# M050B.net
KiCad netlist of a schematic drawn in EAGLE
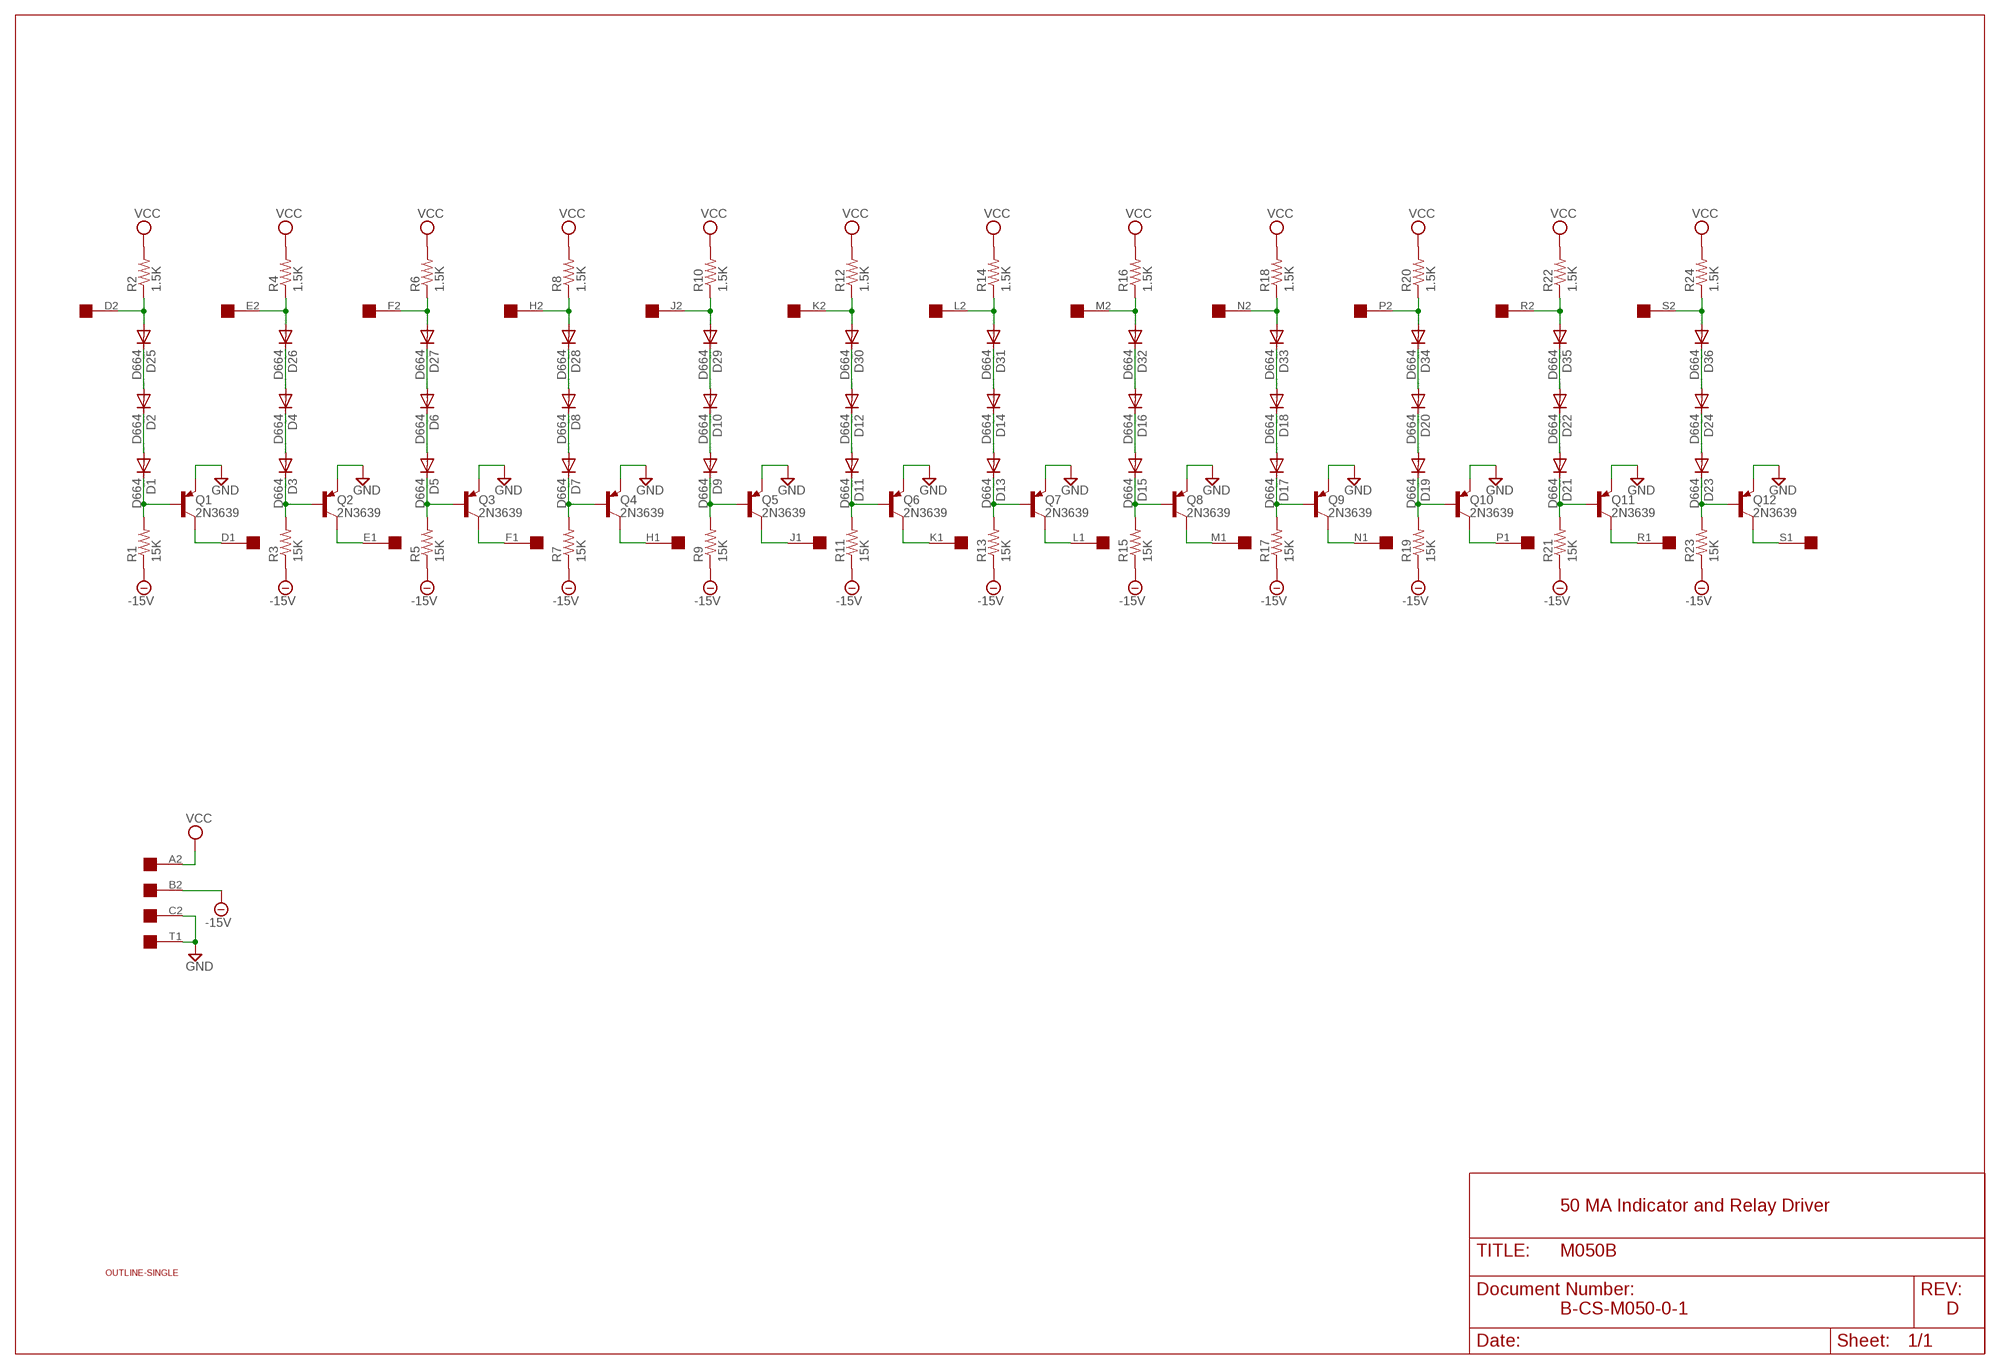
[diagram p0: schematic, sheet 1]

(export (version "E")
  (design (tool "Eeschema 10.0.6"))
  (components
    (comp (ref "D1")
      (value "D664")
      (footprint "eagle-import:DO35-10")
      (libsource (lib "eagle-import") (part "DIODE-DO35-10"))
    )
    (comp (ref "D2")
      (value "D664")
      (footprint "eagle-import:DO35-10")
      (libsource (lib "eagle-import") (part "DIODE-DO35-10"))
    )
    (comp (ref "D3")
      (value "D664")
      (footprint "eagle-import:DO35-10")
      (libsource (lib "eagle-import") (part "DIODE-DO35-10"))
    )
    (comp (ref "D4")
      (value "D664")
      (footprint "eagle-import:DO35-10")
      (libsource (lib "eagle-import") (part "DIODE-DO35-10"))
    )
    (comp (ref "D5")
      (value "D664")
      (footprint "eagle-import:DO35-10")
      (libsource (lib "eagle-import") (part "DIODE-DO35-10"))
    )
    (comp (ref "D6")
      (value "D664")
      (footprint "eagle-import:DO35-10")
      (libsource (lib "eagle-import") (part "DIODE-DO35-10"))
    )
    (comp (ref "D7")
      (value "D664")
      (footprint "eagle-import:DO35-10")
      (libsource (lib "eagle-import") (part "DIODE-DO35-10"))
    )
    (comp (ref "D8")
      (value "D664")
      (footprint "eagle-import:DO35-10")
      (libsource (lib "eagle-import") (part "DIODE-DO35-10"))
    )
    (comp (ref "D9")
      (value "D664")
      (footprint "eagle-import:DO35-10")
      (libsource (lib "eagle-import") (part "DIODE-DO35-10"))
    )
    (comp (ref "D10")
      (value "D664")
      (footprint "eagle-import:DO35-10")
      (libsource (lib "eagle-import") (part "DIODE-DO35-10"))
    )
    (comp (ref "D11")
      (value "D664")
      (footprint "eagle-import:DO35-10")
      (libsource (lib "eagle-import") (part "DIODE-DO35-10"))
    )
    (comp (ref "D12")
      (value "D664")
      (footprint "eagle-import:DO35-10")
      (libsource (lib "eagle-import") (part "DIODE-DO35-10"))
    )
    (comp (ref "D13")
      (value "D664")
      (footprint "eagle-import:DO35-10")
      (libsource (lib "eagle-import") (part "DIODE-DO35-10"))
    )
    (comp (ref "D14")
      (value "D664")
      (footprint "eagle-import:DO35-10")
      (libsource (lib "eagle-import") (part "DIODE-DO35-10"))
    )
    (comp (ref "D15")
      (value "D664")
      (footprint "eagle-import:DO35-10")
      (libsource (lib "eagle-import") (part "DIODE-DO35-10"))
    )
    (comp (ref "D16")
      (value "D664")
      (footprint "eagle-import:DO35-10")
      (libsource (lib "eagle-import") (part "DIODE-DO35-10"))
    )
    (comp (ref "D17")
      (value "D664")
      (footprint "eagle-import:DO35-10")
      (libsource (lib "eagle-import") (part "DIODE-DO35-10"))
    )
    (comp (ref "D18")
      (value "D664")
      (footprint "eagle-import:DO35-10")
      (libsource (lib "eagle-import") (part "DIODE-DO35-10"))
    )
    (comp (ref "D19")
      (value "D664")
      (footprint "eagle-import:DO35-10")
      (libsource (lib "eagle-import") (part "DIODE-DO35-10"))
    )
    (comp (ref "D20")
      (value "D664")
      (footprint "eagle-import:DO35-10")
      (libsource (lib "eagle-import") (part "DIODE-DO35-10"))
    )
    (comp (ref "D21")
      (value "D664")
      (footprint "eagle-import:DO35-10")
      (libsource (lib "eagle-import") (part "DIODE-DO35-10"))
    )
    (comp (ref "D22")
      (value "D664")
      (footprint "eagle-import:DO35-10")
      (libsource (lib "eagle-import") (part "DIODE-DO35-10"))
    )
    (comp (ref "D23")
      (value "D664")
      (footprint "eagle-import:DO35-10")
      (libsource (lib "eagle-import") (part "DIODE-DO35-10"))
    )
    (comp (ref "D24")
      (value "D664")
      (footprint "eagle-import:DO35-10")
      (libsource (lib "eagle-import") (part "DIODE-DO35-10"))
    )
    (comp (ref "D25")
      (value "D664")
      (footprint "eagle-import:DO35-10")
      (libsource (lib "eagle-import") (part "DIODE-DO35-10"))
    )
    (comp (ref "D26")
      (value "D664")
      (footprint "eagle-import:DO35-10")
      (libsource (lib "eagle-import") (part "DIODE-DO35-10"))
    )
    (comp (ref "D27")
      (value "D664")
      (footprint "eagle-import:DO35-10")
      (libsource (lib "eagle-import") (part "DIODE-DO35-10"))
    )
    (comp (ref "D28")
      (value "D664")
      (footprint "eagle-import:DO35-10")
      (libsource (lib "eagle-import") (part "DIODE-DO35-10"))
    )
    (comp (ref "D29")
      (value "D664")
      (footprint "eagle-import:DO35-10")
      (libsource (lib "eagle-import") (part "DIODE-DO35-10"))
    )
    (comp (ref "D30")
      (value "D664")
      (footprint "eagle-import:DO35-10")
      (libsource (lib "eagle-import") (part "DIODE-DO35-10"))
    )
    (comp (ref "D31")
      (value "D664")
      (footprint "eagle-import:DO35-10")
      (libsource (lib "eagle-import") (part "DIODE-DO35-10"))
    )
    (comp (ref "D32")
      (value "D664")
      (footprint "eagle-import:DO35-10")
      (libsource (lib "eagle-import") (part "DIODE-DO35-10"))
    )
    (comp (ref "D33")
      (value "D664")
      (footprint "eagle-import:DO35-10")
      (libsource (lib "eagle-import") (part "DIODE-DO35-10"))
    )
    (comp (ref "D34")
      (value "D664")
      (footprint "eagle-import:DO35-10")
      (libsource (lib "eagle-import") (part "DIODE-DO35-10"))
    )
    (comp (ref "D35")
      (value "D664")
      (footprint "eagle-import:DO35-10")
      (libsource (lib "eagle-import") (part "DIODE-DO35-10"))
    )
    (comp (ref "D36")
      (value "D664")
      (footprint "eagle-import:DO35-10")
      (libsource (lib "eagle-import") (part "DIODE-DO35-10"))
    )
    (comp (ref "Q1")
      (value "2N3639")
      (footprint "eagle-import:TO5")
      (libsource (lib "eagle-import") (part "-PNP-TO5"))
    )
    (comp (ref "Q2")
      (value "2N3639")
      (footprint "eagle-import:TO5")
      (libsource (lib "eagle-import") (part "-PNP-TO5"))
    )
    (comp (ref "Q3")
      (value "2N3639")
      (footprint "eagle-import:TO5")
      (libsource (lib "eagle-import") (part "-PNP-TO5"))
    )
    (comp (ref "Q4")
      (value "2N3639")
      (footprint "eagle-import:TO5")
      (libsource (lib "eagle-import") (part "-PNP-TO5"))
    )
    (comp (ref "Q5")
      (value "2N3639")
      (footprint "eagle-import:TO5")
      (libsource (lib "eagle-import") (part "-PNP-TO5"))
    )
    (comp (ref "Q6")
      (value "2N3639")
      (footprint "eagle-import:TO5")
      (libsource (lib "eagle-import") (part "-PNP-TO5"))
    )
    (comp (ref "Q7")
      (value "2N3639")
      (footprint "eagle-import:TO5")
      (libsource (lib "eagle-import") (part "-PNP-TO5"))
    )
    (comp (ref "Q8")
      (value "2N3639")
      (footprint "eagle-import:TO5")
      (libsource (lib "eagle-import") (part "-PNP-TO5"))
    )
    (comp (ref "Q9")
      (value "2N3639")
      (footprint "eagle-import:TO5")
      (libsource (lib "eagle-import") (part "-PNP-TO5"))
    )
    (comp (ref "Q10")
      (value "2N3639")
      (footprint "eagle-import:TO5")
      (libsource (lib "eagle-import") (part "-PNP-TO5"))
    )
    (comp (ref "Q11")
      (value "2N3639")
      (footprint "eagle-import:TO5")
      (libsource (lib "eagle-import") (part "-PNP-TO5"))
    )
    (comp (ref "Q12")
      (value "2N3639")
      (footprint "eagle-import:TO5")
      (libsource (lib "eagle-import") (part "-PNP-TO5"))
    )
    (comp (ref "R1")
      (value "15K")
      (footprint "eagle-import:0207_10")
      (libsource (lib "eagle-import") (part "R-US_0207/10"))
    )
    (comp (ref "R2")
      (value "1.5K")
      (footprint "eagle-import:0207_10")
      (libsource (lib "eagle-import") (part "R-US_0207/10"))
    )
    (comp (ref "R3")
      (value "15K")
      (footprint "eagle-import:0207_10")
      (libsource (lib "eagle-import") (part "R-US_0207/10"))
    )
    (comp (ref "R4")
      (value "1.5K")
      (footprint "eagle-import:0207_10")
      (libsource (lib "eagle-import") (part "R-US_0207/10"))
    )
    (comp (ref "R5")
      (value "15K")
      (footprint "eagle-import:0207_10")
      (libsource (lib "eagle-import") (part "R-US_0207/10"))
    )
    (comp (ref "R6")
      (value "1.5K")
      (footprint "eagle-import:0207_10")
      (libsource (lib "eagle-import") (part "R-US_0207/10"))
    )
    (comp (ref "R7")
      (value "15K")
      (footprint "eagle-import:0207_10")
      (libsource (lib "eagle-import") (part "R-US_0207/10"))
    )
    (comp (ref "R8")
      (value "1.5K")
      (footprint "eagle-import:0207_10")
      (libsource (lib "eagle-import") (part "R-US_0207/10"))
    )
    (comp (ref "R9")
      (value "15K")
      (footprint "eagle-import:0207_10")
      (libsource (lib "eagle-import") (part "R-US_0207/10"))
    )
    (comp (ref "R10")
      (value "1.5K")
      (footprint "eagle-import:0207_10")
      (libsource (lib "eagle-import") (part "R-US_0207/10"))
    )
    (comp (ref "R11")
      (value "15K")
      (footprint "eagle-import:0207_10")
      (libsource (lib "eagle-import") (part "R-US_0207/10"))
    )
    (comp (ref "R12")
      (value "1.5K")
      (footprint "eagle-import:0207_10")
      (libsource (lib "eagle-import") (part "R-US_0207/10"))
    )
    (comp (ref "R13")
      (value "15K")
      (footprint "eagle-import:0207_10")
      (libsource (lib "eagle-import") (part "R-US_0207/10"))
    )
    (comp (ref "R14")
      (value "1.5K")
      (footprint "eagle-import:0207_10")
      (libsource (lib "eagle-import") (part "R-US_0207/10"))
    )
    (comp (ref "R15")
      (value "15K")
      (footprint "eagle-import:0207_10")
      (libsource (lib "eagle-import") (part "R-US_0207/10"))
    )
    (comp (ref "R16")
      (value "1.5K")
      (footprint "eagle-import:0207_10")
      (libsource (lib "eagle-import") (part "R-US_0207/10"))
    )
    (comp (ref "R17")
      (value "15K")
      (footprint "eagle-import:0207_10")
      (libsource (lib "eagle-import") (part "R-US_0207/10"))
    )
    (comp (ref "R18")
      (value "1.5K")
      (footprint "eagle-import:0207_10")
      (libsource (lib "eagle-import") (part "R-US_0207/10"))
    )
    (comp (ref "R19")
      (value "15K")
      (footprint "eagle-import:0207_10")
      (libsource (lib "eagle-import") (part "R-US_0207/10"))
    )
    (comp (ref "R20")
      (value "1.5K")
      (footprint "eagle-import:0207_10")
      (libsource (lib "eagle-import") (part "R-US_0207/10"))
    )
    (comp (ref "R21")
      (value "15K")
      (footprint "eagle-import:0207_10")
      (libsource (lib "eagle-import") (part "R-US_0207/10"))
    )
    (comp (ref "R22")
      (value "1.5K")
      (footprint "eagle-import:0207_10")
      (libsource (lib "eagle-import") (part "R-US_0207/10"))
    )
    (comp (ref "R23")
      (value "15K")
      (footprint "eagle-import:0207_10")
      (libsource (lib "eagle-import") (part "R-US_0207/10"))
    )
    (comp (ref "R24")
      (value "1.5K")
      (footprint "eagle-import:0207_10")
      (libsource (lib "eagle-import") (part "R-US_0207/10"))
    )
    (comp (ref "U$1")
      (value "OUTLINE-SINGLE")
      (footprint "eagle-import:SINGLE")
      (libsource (lib "eagle-import") (part "OUTLINE-SINGLE"))
    )
    (comp (ref "U$2")
      (value "SINGLE")
      (footprint "eagle-import:EDGE-CON2")
      (libsource (lib "eagle-import") (part "SINGLE"))
    )
  )
  (nets
    (net (code "1") (name "-15V") (class "Default")
      (node (ref "R1") (pin "1") (pinfunction "1_1") (pintype "passive"))
      (node (ref "R11") (pin "1") (pinfunction "1_1") (pintype "passive"))
      (node (ref "R13") (pin "1") (pinfunction "1_1") (pintype "passive"))
      (node (ref "R15") (pin "1") (pinfunction "1_1") (pintype "passive"))
      (node (ref "R17") (pin "1") (pinfunction "1_1") (pintype "passive"))
      (node (ref "R19") (pin "1") (pinfunction "1_1") (pintype "passive"))
      (node (ref "R21") (pin "1") (pinfunction "1_1") (pintype "passive"))
      (node (ref "R23") (pin "1") (pinfunction "1_1") (pintype "passive"))
      (node (ref "R3") (pin "1") (pinfunction "1_1") (pintype "passive"))
      (node (ref "R5") (pin "1") (pinfunction "1_1") (pintype "passive"))
      (node (ref "R7") (pin "1") (pinfunction "1_1") (pintype "passive"))
      (node (ref "R9") (pin "1") (pinfunction "1_1") (pintype "passive"))
      (node (ref "U$2") (pin "B2") (pinfunction "1_B2") (pintype "bidirectional"))
    )
    (net (code "2") (name "GND") (class "Default")
      (node (ref "Q1") (pin "1") (pinfunction "E_1") (pintype "passive"))
      (node (ref "Q10") (pin "1") (pinfunction "E_1") (pintype "passive"))
      (node (ref "Q11") (pin "1") (pinfunction "E_1") (pintype "passive"))
      (node (ref "Q12") (pin "1") (pinfunction "E_1") (pintype "passive"))
      (node (ref "Q2") (pin "1") (pinfunction "E_1") (pintype "passive"))
      (node (ref "Q3") (pin "1") (pinfunction "E_1") (pintype "passive"))
      (node (ref "Q4") (pin "1") (pinfunction "E_1") (pintype "passive"))
      (node (ref "Q5") (pin "1") (pinfunction "E_1") (pintype "passive"))
      (node (ref "Q6") (pin "1") (pinfunction "E_1") (pintype "passive"))
      (node (ref "Q7") (pin "1") (pinfunction "E_1") (pintype "passive"))
      (node (ref "Q8") (pin "1") (pinfunction "E_1") (pintype "passive"))
      (node (ref "Q9") (pin "1") (pinfunction "E_1") (pintype "passive"))
      (node (ref "U$2") (pin "C2") (pinfunction "1_C2") (pintype "bidirectional"))
      (node (ref "U$2") (pin "T1") (pinfunction "1_T1") (pintype "bidirectional"))
    )
    (net (code "3") (name "Net-(D1-PadA)") (class "Default")
      (node (ref "D1") (pin "A") (pinfunction "A_A") (pintype "passive"))
      (node (ref "D2") (pin "C") (pinfunction "C_C") (pintype "passive"))
    )
    (net (code "4") (name "Net-(D2-PadA)") (class "Default")
      (node (ref "D2") (pin "A") (pinfunction "A_A") (pintype "passive"))
      (node (ref "D25") (pin "C") (pinfunction "C_C") (pintype "passive"))
    )
    (net (code "5") (name "Net-(D3-PadA)") (class "Default")
      (node (ref "D3") (pin "A") (pinfunction "A_A") (pintype "passive"))
      (node (ref "D4") (pin "C") (pinfunction "C_C") (pintype "passive"))
    )
    (net (code "6") (name "Net-(D5-PadA)") (class "Default")
      (node (ref "D5") (pin "A") (pinfunction "A_A") (pintype "passive"))
      (node (ref "D6") (pin "C") (pinfunction "C_C") (pintype "passive"))
    )
    (net (code "7") (name "Net-(D7-PadA)") (class "Default")
      (node (ref "D7") (pin "A") (pinfunction "A_A") (pintype "passive"))
      (node (ref "D8") (pin "C") (pinfunction "C_C") (pintype "passive"))
    )
    (net (code "8") (name "Net-(D10-PadA)") (class "Default")
      (node (ref "D10") (pin "A") (pinfunction "A_A") (pintype "passive"))
      (node (ref "D29") (pin "C") (pinfunction "C_C") (pintype "passive"))
    )
    (net (code "9") (name "Net-(D10-PadC)") (class "Default")
      (node (ref "D10") (pin "C") (pinfunction "C_C") (pintype "passive"))
      (node (ref "D9") (pin "A") (pinfunction "A_A") (pintype "passive"))
    )
    (net (code "10") (name "Net-(D11-PadA)") (class "Default")
      (node (ref "D11") (pin "A") (pinfunction "A_A") (pintype "passive"))
      (node (ref "D12") (pin "C") (pinfunction "C_C") (pintype "passive"))
    )
    (net (code "11") (name "Net-(D12-PadA)") (class "Default")
      (node (ref "D12") (pin "A") (pinfunction "A_A") (pintype "passive"))
      (node (ref "D30") (pin "C") (pinfunction "C_C") (pintype "passive"))
    )
    (net (code "12") (name "Net-(D13-PadA)") (class "Default")
      (node (ref "D13") (pin "A") (pinfunction "A_A") (pintype "passive"))
      (node (ref "D14") (pin "C") (pinfunction "C_C") (pintype "passive"))
    )
    (net (code "13") (name "Net-(D14-PadA)") (class "Default")
      (node (ref "D14") (pin "A") (pinfunction "A_A") (pintype "passive"))
      (node (ref "D31") (pin "C") (pinfunction "C_C") (pintype "passive"))
    )
    (net (code "14") (name "Net-(D15-PadA)") (class "Default")
      (node (ref "D15") (pin "A") (pinfunction "A_A") (pintype "passive"))
      (node (ref "D16") (pin "C") (pinfunction "C_C") (pintype "passive"))
    )
    (net (code "15") (name "Net-(D16-PadA)") (class "Default")
      (node (ref "D16") (pin "A") (pinfunction "A_A") (pintype "passive"))
      (node (ref "D32") (pin "C") (pinfunction "C_C") (pintype "passive"))
    )
    (net (code "16") (name "Net-(D17-PadA)") (class "Default")
      (node (ref "D17") (pin "A") (pinfunction "A_A") (pintype "passive"))
      (node (ref "D18") (pin "C") (pinfunction "C_C") (pintype "passive"))
    )
    (net (code "17") (name "Net-(D18-PadA)") (class "Default")
      (node (ref "D18") (pin "A") (pinfunction "A_A") (pintype "passive"))
      (node (ref "D33") (pin "C") (pinfunction "C_C") (pintype "passive"))
    )
    (net (code "18") (name "Net-(D19-PadA)") (class "Default")
      (node (ref "D19") (pin "A") (pinfunction "A_A") (pintype "passive"))
      (node (ref "D20") (pin "C") (pinfunction "C_C") (pintype "passive"))
    )
    (net (code "19") (name "Net-(D20-PadA)") (class "Default")
      (node (ref "D20") (pin "A") (pinfunction "A_A") (pintype "passive"))
      (node (ref "D34") (pin "C") (pinfunction "C_C") (pintype "passive"))
    )
    (net (code "20") (name "Net-(D21-PadA)") (class "Default")
      (node (ref "D21") (pin "A") (pinfunction "A_A") (pintype "passive"))
      (node (ref "D22") (pin "C") (pinfunction "C_C") (pintype "passive"))
    )
    (net (code "21") (name "Net-(D22-PadA)") (class "Default")
      (node (ref "D22") (pin "A") (pinfunction "A_A") (pintype "passive"))
      (node (ref "D35") (pin "C") (pinfunction "C_C") (pintype "passive"))
    )
    (net (code "22") (name "Net-(D23-PadA)") (class "Default")
      (node (ref "D23") (pin "A") (pinfunction "A_A") (pintype "passive"))
      (node (ref "D24") (pin "C") (pinfunction "C_C") (pintype "passive"))
    )
    (net (code "23") (name "Net-(D24-PadA)") (class "Default")
      (node (ref "D24") (pin "A") (pinfunction "A_A") (pintype "passive"))
      (node (ref "D36") (pin "C") (pinfunction "C_C") (pintype "passive"))
    )
    (net (code "24") (name "Net-(D26-PadC)") (class "Default")
      (node (ref "D26") (pin "C") (pinfunction "C_C") (pintype "passive"))
      (node (ref "D4") (pin "A") (pinfunction "A_A") (pintype "passive"))
    )
    (net (code "25") (name "Net-(D27-PadC)") (class "Default")
      (node (ref "D27") (pin "C") (pinfunction "C_C") (pintype "passive"))
      (node (ref "D6") (pin "A") (pinfunction "A_A") (pintype "passive"))
    )
    (net (code "26") (name "Net-(D28-PadC)") (class "Default")
      (node (ref "D28") (pin "C") (pinfunction "C_C") (pintype "passive"))
      (node (ref "D8") (pin "A") (pinfunction "A_A") (pintype "passive"))
    )
    (net (code "27") (name "Net-(Q1-B)") (class "Default")
      (node (ref "D1") (pin "C") (pinfunction "C_C") (pintype "passive"))
      (node (ref "Q1") (pin "2") (pinfunction "B_2") (pintype "passive"))
      (node (ref "R1") (pin "2") (pinfunction "2_2") (pintype "passive"))
    )
    (net (code "28") (name "Net-(Q1-C)") (class "Default")
      (node (ref "Q1") (pin "3") (pinfunction "C_3") (pintype "passive"))
      (node (ref "U$2") (pin "D1") (pinfunction "1_D1") (pintype "bidirectional"))
    )
    (net (code "29") (name "Net-(Q2-B)") (class "Default")
      (node (ref "D3") (pin "C") (pinfunction "C_C") (pintype "passive"))
      (node (ref "Q2") (pin "2") (pinfunction "B_2") (pintype "passive"))
      (node (ref "R3") (pin "2") (pinfunction "2_2") (pintype "passive"))
    )
    (net (code "30") (name "Net-(Q2-C)") (class "Default")
      (node (ref "Q2") (pin "3") (pinfunction "C_3") (pintype "passive"))
      (node (ref "U$2") (pin "E1") (pinfunction "1_E1") (pintype "bidirectional"))
    )
    (net (code "31") (name "Net-(Q3-B)") (class "Default")
      (node (ref "D5") (pin "C") (pinfunction "C_C") (pintype "passive"))
      (node (ref "Q3") (pin "2") (pinfunction "B_2") (pintype "passive"))
      (node (ref "R5") (pin "2") (pinfunction "2_2") (pintype "passive"))
    )
    (net (code "32") (name "Net-(Q3-C)") (class "Default")
      (node (ref "Q3") (pin "3") (pinfunction "C_3") (pintype "passive"))
      (node (ref "U$2") (pin "F1") (pinfunction "1_F1") (pintype "bidirectional"))
    )
    (net (code "33") (name "Net-(Q4-B)") (class "Default")
      (node (ref "D7") (pin "C") (pinfunction "C_C") (pintype "passive"))
      (node (ref "Q4") (pin "2") (pinfunction "B_2") (pintype "passive"))
      (node (ref "R7") (pin "2") (pinfunction "2_2") (pintype "passive"))
    )
    (net (code "34") (name "Net-(Q4-C)") (class "Default")
      (node (ref "Q4") (pin "3") (pinfunction "C_3") (pintype "passive"))
      (node (ref "U$2") (pin "H1") (pinfunction "1_H1") (pintype "bidirectional"))
    )
    (net (code "35") (name "Net-(Q5-B)") (class "Default")
      (node (ref "D9") (pin "C") (pinfunction "C_C") (pintype "passive"))
      (node (ref "Q5") (pin "2") (pinfunction "B_2") (pintype "passive"))
      (node (ref "R9") (pin "2") (pinfunction "2_2") (pintype "passive"))
    )
    (net (code "36") (name "Net-(Q5-C)") (class "Default")
      (node (ref "Q5") (pin "3") (pinfunction "C_3") (pintype "passive"))
      (node (ref "U$2") (pin "J1") (pinfunction "1_J1") (pintype "bidirectional"))
    )
    (net (code "37") (name "Net-(Q6-B)") (class "Default")
      (node (ref "D11") (pin "C") (pinfunction "C_C") (pintype "passive"))
      (node (ref "Q6") (pin "2") (pinfunction "B_2") (pintype "passive"))
      (node (ref "R11") (pin "2") (pinfunction "2_2") (pintype "passive"))
    )
    (net (code "38") (name "Net-(Q6-C)") (class "Default")
      (node (ref "Q6") (pin "3") (pinfunction "C_3") (pintype "passive"))
      (node (ref "U$2") (pin "K1") (pinfunction "1_K1") (pintype "bidirectional"))
    )
    (net (code "39") (name "Net-(Q7-B)") (class "Default")
      (node (ref "D13") (pin "C") (pinfunction "C_C") (pintype "passive"))
      (node (ref "Q7") (pin "2") (pinfunction "B_2") (pintype "passive"))
      (node (ref "R13") (pin "2") (pinfunction "2_2") (pintype "passive"))
    )
    (net (code "40") (name "Net-(Q7-C)") (class "Default")
      (node (ref "Q7") (pin "3") (pinfunction "C_3") (pintype "passive"))
      (node (ref "U$2") (pin "L1") (pinfunction "1_L1") (pintype "bidirectional"))
    )
    (net (code "41") (name "Net-(Q8-B)") (class "Default")
      (node (ref "D15") (pin "C") (pinfunction "C_C") (pintype "passive"))
      (node (ref "Q8") (pin "2") (pinfunction "B_2") (pintype "passive"))
      (node (ref "R15") (pin "2") (pinfunction "2_2") (pintype "passive"))
    )
    (net (code "42") (name "Net-(Q8-C)") (class "Default")
      (node (ref "Q8") (pin "3") (pinfunction "C_3") (pintype "passive"))
      (node (ref "U$2") (pin "M1") (pinfunction "1_M1") (pintype "bidirectional"))
    )
    (net (code "43") (name "Net-(Q9-B)") (class "Default")
      (node (ref "D17") (pin "C") (pinfunction "C_C") (pintype "passive"))
      (node (ref "Q9") (pin "2") (pinfunction "B_2") (pintype "passive"))
      (node (ref "R17") (pin "2") (pinfunction "2_2") (pintype "passive"))
    )
    (net (code "44") (name "Net-(Q9-C)") (class "Default")
      (node (ref "Q9") (pin "3") (pinfunction "C_3") (pintype "passive"))
      (node (ref "U$2") (pin "N1") (pinfunction "1_N1") (pintype "bidirectional"))
    )
    (net (code "45") (name "Net-(Q10-B)") (class "Default")
      (node (ref "D19") (pin "C") (pinfunction "C_C") (pintype "passive"))
      (node (ref "Q10") (pin "2") (pinfunction "B_2") (pintype "passive"))
      (node (ref "R19") (pin "2") (pinfunction "2_2") (pintype "passive"))
    )
    (net (code "46") (name "Net-(Q10-C)") (class "Default")
      (node (ref "Q10") (pin "3") (pinfunction "C_3") (pintype "passive"))
      (node (ref "U$2") (pin "P1") (pinfunction "1_P1") (pintype "bidirectional"))
    )
    (net (code "47") (name "Net-(Q11-B)") (class "Default")
      (node (ref "D21") (pin "C") (pinfunction "C_C") (pintype "passive"))
      (node (ref "Q11") (pin "2") (pinfunction "B_2") (pintype "passive"))
      (node (ref "R21") (pin "2") (pinfunction "2_2") (pintype "passive"))
    )
    (net (code "48") (name "Net-(Q11-C)") (class "Default")
      (node (ref "Q11") (pin "3") (pinfunction "C_3") (pintype "passive"))
      (node (ref "U$2") (pin "R1") (pinfunction "1_R1") (pintype "bidirectional"))
    )
    (net (code "49") (name "Net-(Q12-B)") (class "Default")
      (node (ref "D23") (pin "C") (pinfunction "C_C") (pintype "passive"))
      (node (ref "Q12") (pin "2") (pinfunction "B_2") (pintype "passive"))
      (node (ref "R23") (pin "2") (pinfunction "2_2") (pintype "passive"))
    )
    (net (code "50") (name "Net-(Q12-C)") (class "Default")
      (node (ref "Q12") (pin "3") (pinfunction "C_3") (pintype "passive"))
      (node (ref "U$2") (pin "S1") (pinfunction "1_S1") (pintype "bidirectional"))
    )
    (net (code "51") (name "Net-(U$2AB-1)") (class "Default")
      (node (ref "D35") (pin "A") (pinfunction "A_A") (pintype "passive"))
      (node (ref "R22") (pin "1") (pinfunction "1_1") (pintype "passive"))
      (node (ref "U$2") (pin "R2") (pinfunction "1_R2") (pintype "bidirectional"))
    )
    (net (code "52") (name "Net-(U$2AD-1)") (class "Default")
      (node (ref "D36") (pin "A") (pinfunction "A_A") (pintype "passive"))
      (node (ref "R24") (pin "1") (pinfunction "1_1") (pintype "passive"))
      (node (ref "U$2") (pin "S2") (pinfunction "1_S2") (pintype "bidirectional"))
    )
    (net (code "53") (name "Net-(U$2H-1)") (class "Default")
      (node (ref "D25") (pin "A") (pinfunction "A_A") (pintype "passive"))
      (node (ref "R2") (pin "1") (pinfunction "1_1") (pintype "passive"))
      (node (ref "U$2") (pin "D2") (pinfunction "1_D2") (pintype "bidirectional"))
    )
    (net (code "54") (name "Net-(U$2J-1)") (class "Default")
      (node (ref "D26") (pin "A") (pinfunction "A_A") (pintype "passive"))
      (node (ref "R4") (pin "1") (pinfunction "1_1") (pintype "passive"))
      (node (ref "U$2") (pin "E2") (pinfunction "1_E2") (pintype "bidirectional"))
    )
    (net (code "55") (name "Net-(U$2L-1)") (class "Default")
      (node (ref "D27") (pin "A") (pinfunction "A_A") (pintype "passive"))
      (node (ref "R6") (pin "1") (pinfunction "1_1") (pintype "passive"))
      (node (ref "U$2") (pin "F2") (pinfunction "1_F2") (pintype "bidirectional"))
    )
    (net (code "56") (name "Net-(U$2N-1)") (class "Default")
      (node (ref "D28") (pin "A") (pinfunction "A_A") (pintype "passive"))
      (node (ref "R8") (pin "1") (pinfunction "1_1") (pintype "passive"))
      (node (ref "U$2") (pin "H2") (pinfunction "1_H2") (pintype "bidirectional"))
    )
    (net (code "57") (name "Net-(U$2P-1)") (class "Default")
      (node (ref "D29") (pin "A") (pinfunction "A_A") (pintype "passive"))
      (node (ref "R10") (pin "1") (pinfunction "1_1") (pintype "passive"))
      (node (ref "U$2") (pin "J2") (pinfunction "1_J2") (pintype "bidirectional"))
    )
    (net (code "58") (name "Net-(U$2R-1)") (class "Default")
      (node (ref "D30") (pin "A") (pinfunction "A_A") (pintype "passive"))
      (node (ref "R12") (pin "1") (pinfunction "1_1") (pintype "passive"))
      (node (ref "U$2") (pin "K2") (pinfunction "1_K2") (pintype "bidirectional"))
    )
    (net (code "59") (name "Net-(U$2T-1)") (class "Default")
      (node (ref "D31") (pin "A") (pinfunction "A_A") (pintype "passive"))
      (node (ref "R14") (pin "1") (pinfunction "1_1") (pintype "passive"))
      (node (ref "U$2") (pin "L2") (pinfunction "1_L2") (pintype "bidirectional"))
    )
    (net (code "60") (name "Net-(U$2V-1)") (class "Default")
      (node (ref "D32") (pin "A") (pinfunction "A_A") (pintype "passive"))
      (node (ref "R16") (pin "1") (pinfunction "1_1") (pintype "passive"))
      (node (ref "U$2") (pin "M2") (pinfunction "1_M2") (pintype "bidirectional"))
    )
    (net (code "61") (name "Net-(U$2X-1)") (class "Default")
      (node (ref "D33") (pin "A") (pinfunction "A_A") (pintype "passive"))
      (node (ref "R18") (pin "1") (pinfunction "1_1") (pintype "passive"))
      (node (ref "U$2") (pin "N2") (pinfunction "1_N2") (pintype "bidirectional"))
    )
    (net (code "62") (name "Net-(U$2Z-1)") (class "Default")
      (node (ref "D34") (pin "A") (pinfunction "A_A") (pintype "passive"))
      (node (ref "R20") (pin "1") (pinfunction "1_1") (pintype "passive"))
      (node (ref "U$2") (pin "P2") (pinfunction "1_P2") (pintype "bidirectional"))
    )
    (net (code "63") (name "VCC") (class "Default")
      (node (ref "R10") (pin "2") (pinfunction "2_2") (pintype "passive"))
      (node (ref "R12") (pin "2") (pinfunction "2_2") (pintype "passive"))
      (node (ref "R14") (pin "2") (pinfunction "2_2") (pintype "passive"))
      (node (ref "R16") (pin "2") (pinfunction "2_2") (pintype "passive"))
      (node (ref "R18") (pin "2") (pinfunction "2_2") (pintype "passive"))
      (node (ref "R2") (pin "2") (pinfunction "2_2") (pintype "passive"))
      (node (ref "R20") (pin "2") (pinfunction "2_2") (pintype "passive"))
      (node (ref "R22") (pin "2") (pinfunction "2_2") (pintype "passive"))
      (node (ref "R24") (pin "2") (pinfunction "2_2") (pintype "passive"))
      (node (ref "R4") (pin "2") (pinfunction "2_2") (pintype "passive"))
      (node (ref "R6") (pin "2") (pinfunction "2_2") (pintype "passive"))
      (node (ref "R8") (pin "2") (pinfunction "2_2") (pintype "passive"))
      (node (ref "U$2") (pin "A2") (pinfunction "1_A2") (pintype "bidirectional"))
    )
  )
)
